# VREG_RT9166-13PVL.net
KiCad netlist of a schematic drawn in Altium Designer
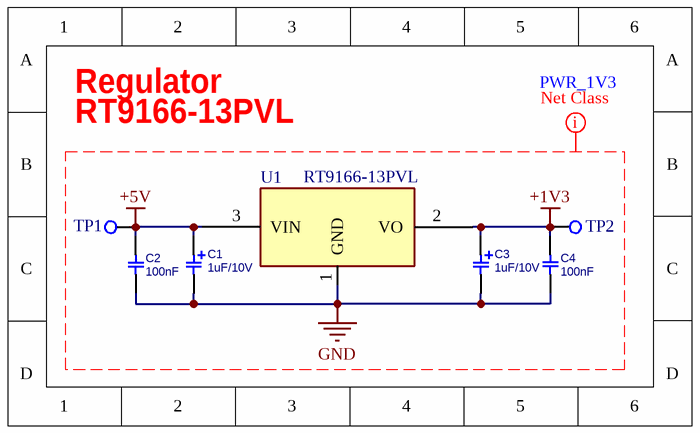
[diagram p0: VREG RT9166-13PVL.SchDoc]

(export (version "E")
  (design (tool "Eeschema 10.0.6"))
  (components
    (comp (ref "C1")
      (value "1uF/10V")
      (footprint "C_TN_A")
      (description "CAP, SMD, TAN")
      (libsource (lib "PW Components 97_492") (part "CAP_SMD_TAN"))
    )
    (comp (ref "C2")
      (value "100nF")
      (footprint "C0603S")
      (description "CAP, SMD, MLCC")
      (fields (field (name "MANF_P#") "MANF_PART#") (field (name "MANF") "Murata"))
      (libsource (lib "Passive") (part "CAP_SMD_MLCC"))
    )
    (comp (ref "C3")
      (value "1uF/10V")
      (footprint "C_TN_A")
      (description "CAP, SMD, TAN")
      (libsource (lib "PW Components 97_492") (part "CAP_SMD_TAN"))
    )
    (comp (ref "C4")
      (value "100nF")
      (footprint "C0603S")
      (description "CAP, SMD, MLCC")
      (fields (field (name "MANF_P#") "MANF_PART#") (field (name "MANF") "Murata"))
      (libsource (lib "Passive") (part "CAP_SMD_MLCC"))
    )
    (comp (ref "TP1")
      (value "Test Point")
      (footprint "TPSMD_C1")
      (libsource (lib "Passives") (part "Test Point"))
    )
    (comp (ref "TP2")
      (value "Test Point")
      (footprint "TPSMD_C1")
      (libsource (lib "Passives") (part "Test Point"))
    )
    (comp (ref "U1")
      (value "RT9166-13PVL")
      (footprint "SOT23_3")
      (description "REG, Linear, Fixed, 1.3v, 0.3A/0.6A, SOT23")
      (fields (field (name "MANF") "TI"))
      (libsource (lib "PW Components 97_481") (part "VREG_RT9166A-13PVL_SOT23"))
    )
  )
  (nets
    (net (code "1") (name "+1V3") (class "Default")
      (node (ref "C3") (pin "1") (pinfunction "1_1") (pintype "passive"))
      (node (ref "C4") (pin "1") (pinfunction "1_1") (pintype "passive"))
      (node (ref "TP2") (pin "1") (pinfunction "TP_1") (pintype "passive"))
      (node (ref "U1") (pin "2") (pinfunction "VO_2") (pintype "passive"))
    )
    (net (code "2") (name "+5V") (class "Default")
      (node (ref "C1") (pin "1") (pinfunction "1_1") (pintype "passive"))
      (node (ref "C2") (pin "1") (pinfunction "1_1") (pintype "passive"))
      (node (ref "TP1") (pin "1") (pinfunction "TP_1") (pintype "passive"))
      (node (ref "U1") (pin "3") (pinfunction "VIN_3") (pintype "passive"))
    )
    (net (code "3") (name "GND") (class "Default")
      (node (ref "C1") (pin "2") (pinfunction "2_2") (pintype "passive"))
      (node (ref "C2") (pin "2") (pinfunction "2_2") (pintype "passive"))
      (node (ref "C3") (pin "2") (pinfunction "2_2") (pintype "passive"))
      (node (ref "C4") (pin "2") (pinfunction "2_2") (pintype "passive"))
      (node (ref "U1") (pin "1") (pinfunction "GND_1") (pintype "passive"))
    )
  )
)
